# Transformer.net
KiCad netlist of a schematic drawn in Altium Designer
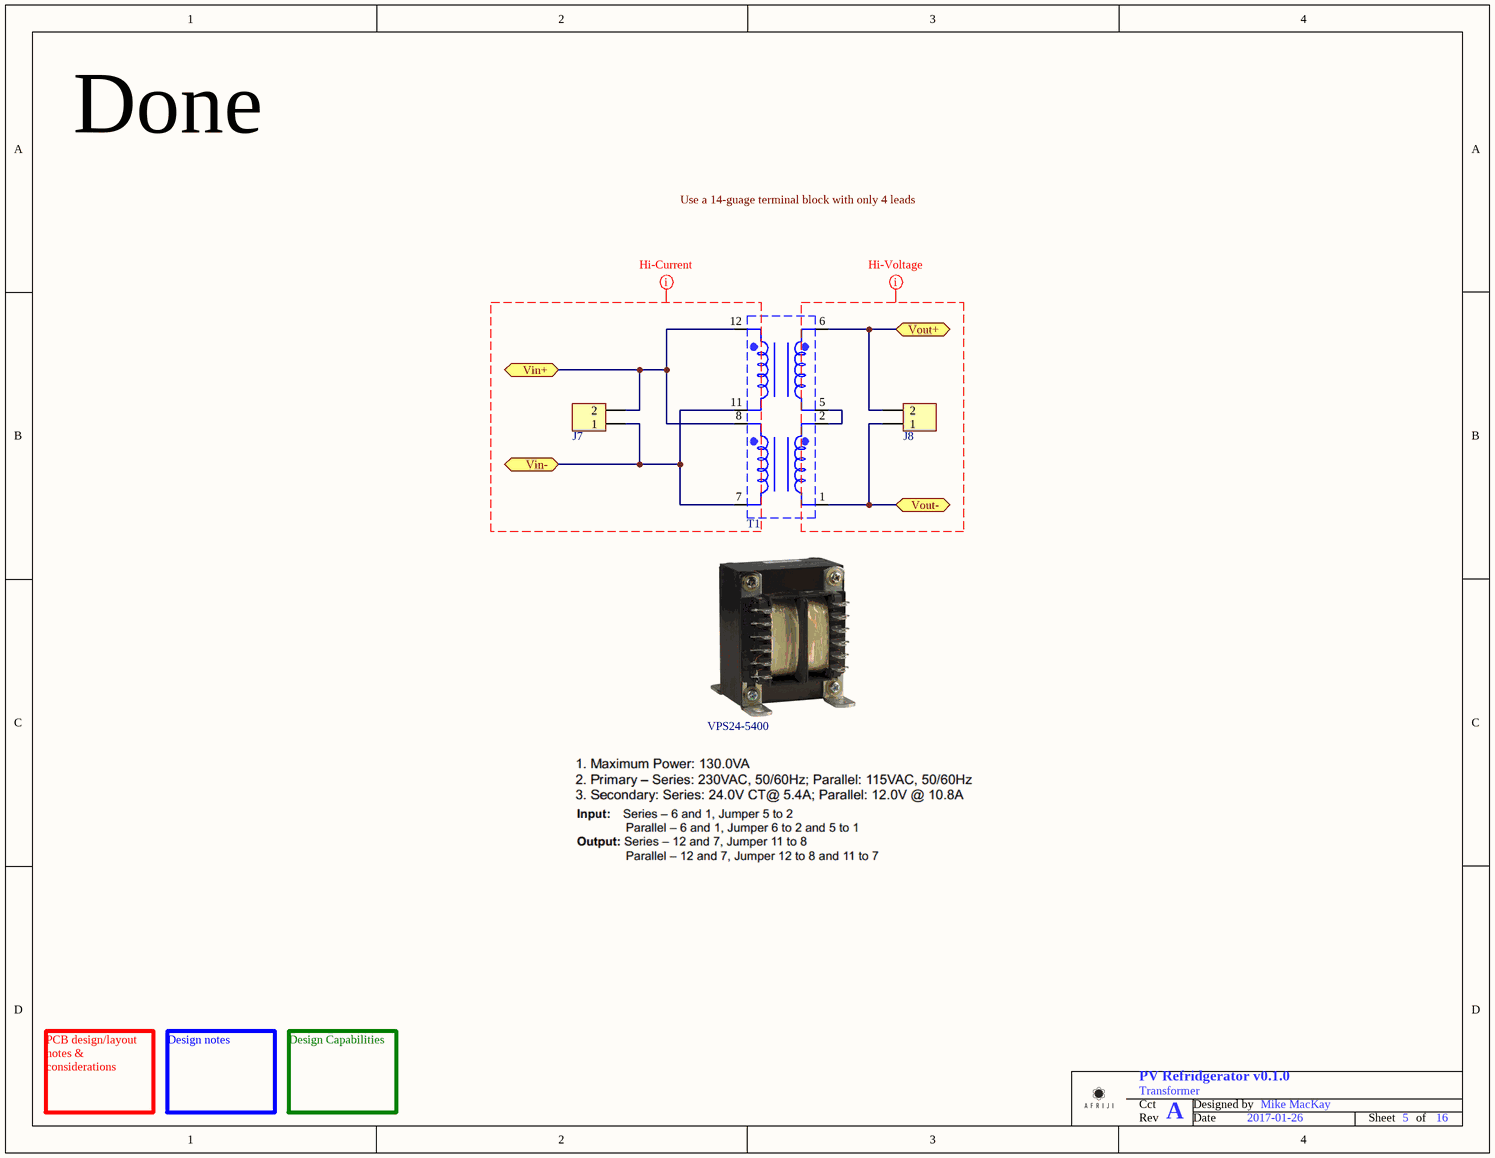
[diagram p0: Transformer.SchDoc]

(export (version "E")
  (design (tool "Eeschema 10.0.6"))
  (components
    (comp (ref "J7")
      (value "Terminal Block - 2-Position HiV/HiA")
      (footprint "TE 796739-2")
      (fields
        (field (name "MANUFACTURER") "TE Connectivity AMP Connectors")
        (field (name "MANUFACTURER PART NUMBER") "796739-2")
        (field (name "VOLTAGE") "600V")
      )
      (libsource (lib "") (part "Terminal Block - 2-Position HiV/HiA_1"))
    )
    (comp (ref "J8")
      (value "Terminal Block - 2-Position HiV/HiA")
      (footprint "TE 796739-2")
      (fields
        (field (name "MANUFACTURER") "TE Connectivity AMP Connectors")
        (field (name "MANUFACTURER PART NUMBER") "796739-2")
        (field (name "VOLTAGE") "600V")
      )
      (libsource (lib "Local Library") (part "Terminal Block - 2-Position HiV/HiA"))
    )
    (comp (ref "T1")
      (value "Transformer Connector")
      (libsource (lib "Local Library") (part "Transformer Connector"))
    )
    (comp (ref "Transformer1")
      (value "Transformer")
      (footprint "Transformer")
      (fields
        (field (name "MANUFACTURER") "Triad Magnetics")
        (field (name "MANUFACTURER PART NUMBER") "VPS24-5400")
      )
      (libsource (lib "Local Library") (part "Transformer"))
    )
  )
  (nets
    (net (code "2") (name "/Vin+") (class "Default")
      (node (ref "J7") (pin "2") (pinfunction "2_2") (pintype "passive"))
      (node (ref "T1") (pin "12") (pinfunction "12_12") (pintype "passive"))
      (node (ref "T1") (pin "8") (pinfunction "8_8") (pintype "passive"))
    )
    (net (code "3") (name "/Vin-") (class "Default")
      (node (ref "J7") (pin "1") (pinfunction "1_1") (pintype "passive"))
      (node (ref "T1") (pin "11") (pinfunction "11_11") (pintype "passive"))
      (node (ref "T1") (pin "7") (pinfunction "7_7") (pintype "passive"))
    )
    (net (code "4") (name "/Vout+") (class "Default")
      (node (ref "J8") (pin "2") (pinfunction "2_2") (pintype "passive"))
      (node (ref "T1") (pin "6") (pinfunction "6_6") (pintype "passive"))
    )
    (net (code "5") (name "/Vout-") (class "Default")
      (node (ref "J8") (pin "1") (pinfunction "1_1") (pintype "passive"))
      (node (ref "T1") (pin "1") (pinfunction "1_1") (pintype "passive"))
    )
    (net (code "6") (name "Net-(T1-Pad2)") (class "Default")
      (node (ref "T1") (pin "2") (pinfunction "2_2") (pintype "passive"))
      (node (ref "T1") (pin "5") (pinfunction "5_5") (pintype "passive"))
    )
  )
)
